# board.net
KiCad netlist of a schematic drawn in EAGLE
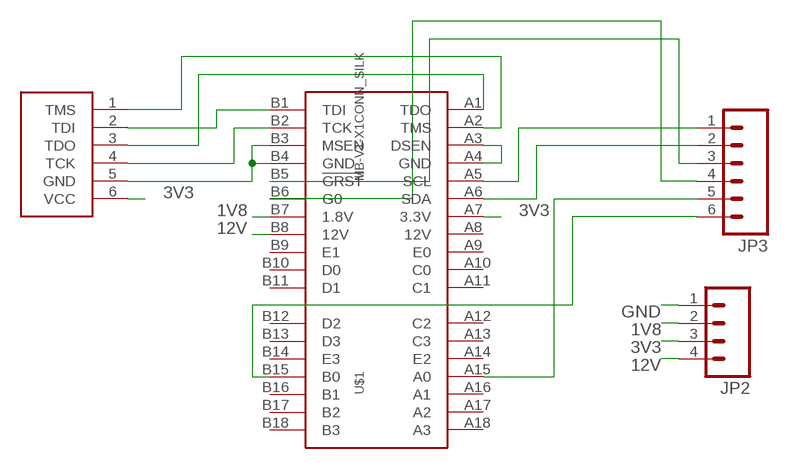
[diagram p0: schematic, sheet 1]

(export (version "E")
  (design (tool "Eeschema 10.0.6"))
  (components
    (comp (ref "JP2")
      (value "M04PTH")
      (footprint "eagle-import:1X04")
      (libsource (lib "eagle-import") (part "M04PTH"))
    )
    (comp (ref "JP3")
      (value "M06SIP")
      (footprint "eagle-import:1X06")
      (libsource (lib "eagle-import") (part "M06SIP"))
    )
    (comp (ref "U$1")
      (value "MB-V1-X1CONN_SILK")
      (footprint "eagle-import:MB-V1-X1-CONN")
      (libsource (lib "eagle-import") (part "MB-V1-X1CONN_SILK"))
    )
    (comp (ref "U$2")
      (value "JTAGDIGILENT")
      (footprint "eagle-import:1X06")
      (libsource (lib "eagle-import") (part "JTAGDIGILENT"))
    )
  )
  (nets
    (net (code "1") (name "/1V8") (class "Default")
      (node (ref "JP2") (pin "2") (pinfunction "2_2") (pintype "passive"))
      (node (ref "U$1") (pin "B7") (pinfunction "1.8V_B7") (pintype "bidirectional"))
    )
    (net (code "2") (name "/3V3") (class "Default")
      (node (ref "JP2") (pin "3") (pinfunction "3_3") (pintype "passive"))
      (node (ref "U$1") (pin "A7") (pinfunction "3.3V_A7") (pintype "bidirectional"))
      (node (ref "U$2") (pin "6") (pinfunction "VCC_6") (pintype "bidirectional"))
    )
    (net (code "3") (name "/12V") (class "Default")
      (node (ref "JP2") (pin "4") (pinfunction "4_4") (pintype "passive"))
      (node (ref "U$1") (pin "B8") (pinfunction "12V_B8") (pintype "bidirectional"))
    )
    (net (code "4") (name "/GND") (class "Default")
      (node (ref "JP2") (pin "1") (pinfunction "1_1") (pintype "passive"))
      (node (ref "U$1") (pin "B3") (pinfunction "MSEN_B3") (pintype "bidirectional"))
      (node (ref "U$1") (pin "B4") (pinfunction "GND_B4") (pintype "bidirectional"))
      (node (ref "U$2") (pin "5") (pinfunction "GND_5") (pintype "bidirectional"))
    )
    (net (code "5") (name "Net-(U$1-A0)") (class "Default")
      (node (ref "JP3") (pin "5") (pinfunction "5_5") (pintype "passive"))
      (node (ref "U$1") (pin "A15") (pinfunction "A0_A15") (pintype "bidirectional"))
    )
    (net (code "6") (name "Net-(U$1-B0)") (class "Default")
      (node (ref "JP3") (pin "6") (pinfunction "6_6") (pintype "passive"))
      (node (ref "U$1") (pin "B15") (pinfunction "B0_B15") (pintype "bidirectional"))
    )
    (net (code "7") (name "Net-(U$1-DSEN)") (class "Default")
      (node (ref "U$1") (pin "A3") (pinfunction "DSEN_A3") (pintype "bidirectional"))
      (node (ref "U$1") (pin "A4") (pinfunction "GND_A4") (pintype "bidirectional"))
    )
    (net (code "8") (name "Net-(U$1-G0)") (class "Default")
      (node (ref "JP3") (pin "4") (pinfunction "4_4") (pintype "passive"))
      (node (ref "U$1") (pin "B6") (pinfunction "G0_B6") (pintype "bidirectional"))
    )
    (net (code "9") (name "Net-(U$1-SCL)") (class "Default")
      (node (ref "JP3") (pin "1") (pinfunction "1_1") (pintype "passive"))
      (node (ref "U$1") (pin "A5") (pinfunction "SCL_A5") (pintype "bidirectional"))
    )
    (net (code "10") (name "Net-(U$1-SDA)") (class "Default")
      (node (ref "JP3") (pin "2") (pinfunction "2_2") (pintype "passive"))
      (node (ref "U$1") (pin "A6") (pinfunction "SDA_A6") (pintype "bidirectional"))
    )
    (net (code "11") (name "Net-(U$1-TCK)") (class "Default")
      (node (ref "U$1") (pin "B2") (pinfunction "TCK_B2") (pintype "bidirectional"))
      (node (ref "U$2") (pin "4") (pinfunction "TCK_4") (pintype "bidirectional"))
    )
    (net (code "12") (name "Net-(U$1-TDI)") (class "Default")
      (node (ref "U$1") (pin "B1") (pinfunction "TDI_B1") (pintype "bidirectional"))
      (node (ref "U$2") (pin "2") (pinfunction "TDI_2") (pintype "bidirectional"))
    )
    (net (code "13") (name "Net-(U$1-TDO)") (class "Default")
      (node (ref "U$1") (pin "A1") (pinfunction "TDO_A1") (pintype "bidirectional"))
      (node (ref "U$2") (pin "3") (pinfunction "TDO_3") (pintype "bidirectional"))
    )
    (net (code "14") (name "Net-(U$1-TMS)") (class "Default")
      (node (ref "U$1") (pin "A2") (pinfunction "TMS_A2") (pintype "bidirectional"))
      (node (ref "U$2") (pin "1") (pinfunction "TMS_1") (pintype "bidirectional"))
    )
    (net (code "15") (name "Net-(U$1-~{GRST})") (class "Default")
      (node (ref "JP3") (pin "3") (pinfunction "3_3") (pintype "passive"))
      (node (ref "U$1") (pin "B5") (pinfunction "~{GRST}_B5") (pintype "bidirectional"))
    )
    (net (code "16") (name "unconnected-(U$1-12V-PadA8)") (class "Default")
      (node (ref "U$1") (pin "A8") (pinfunction "12V_A8") (pintype "bidirectional"))
    )
    (net (code "17") (name "unconnected-(U$1-A1-PadA16)") (class "Default")
      (node (ref "U$1") (pin "A16") (pinfunction "A1_A16") (pintype "bidirectional"))
    )
    (net (code "18") (name "unconnected-(U$1-A2-PadA17)") (class "Default")
      (node (ref "U$1") (pin "A17") (pinfunction "A2_A17") (pintype "bidirectional"))
    )
    (net (code "19") (name "unconnected-(U$1-A3-PadA18)") (class "Default")
      (node (ref "U$1") (pin "A18") (pinfunction "A3_A18") (pintype "bidirectional"))
    )
    (net (code "20") (name "unconnected-(U$1-B1-PadB16)") (class "Default")
      (node (ref "U$1") (pin "B16") (pinfunction "B1_B16") (pintype "bidirectional"))
    )
    (net (code "21") (name "unconnected-(U$1-B2-PadB17)") (class "Default")
      (node (ref "U$1") (pin "B17") (pinfunction "B2_B17") (pintype "bidirectional"))
    )
    (net (code "22") (name "unconnected-(U$1-B3-PadB18)") (class "Default")
      (node (ref "U$1") (pin "B18") (pinfunction "B3_B18") (pintype "bidirectional"))
    )
    (net (code "23") (name "unconnected-(U$1-C0-PadA10)") (class "Default")
      (node (ref "U$1") (pin "A10") (pinfunction "C0_A10") (pintype "bidirectional"))
    )
    (net (code "24") (name "unconnected-(U$1-C1-PadA11)") (class "Default")
      (node (ref "U$1") (pin "A11") (pinfunction "C1_A11") (pintype "bidirectional"))
    )
    (net (code "25") (name "unconnected-(U$1-C2-PadA12)") (class "Default")
      (node (ref "U$1") (pin "A12") (pinfunction "C2_A12") (pintype "bidirectional"))
    )
    (net (code "26") (name "unconnected-(U$1-C3-PadA13)") (class "Default")
      (node (ref "U$1") (pin "A13") (pinfunction "C3_A13") (pintype "bidirectional"))
    )
    (net (code "27") (name "unconnected-(U$1-D0-PadB10)") (class "Default")
      (node (ref "U$1") (pin "B10") (pinfunction "D0_B10") (pintype "bidirectional"))
    )
    (net (code "28") (name "unconnected-(U$1-D1-PadB11)") (class "Default")
      (node (ref "U$1") (pin "B11") (pinfunction "D1_B11") (pintype "bidirectional"))
    )
    (net (code "29") (name "unconnected-(U$1-D2-PadB12)") (class "Default")
      (node (ref "U$1") (pin "B12") (pinfunction "D2_B12") (pintype "bidirectional"))
    )
    (net (code "30") (name "unconnected-(U$1-D3-PadB13)") (class "Default")
      (node (ref "U$1") (pin "B13") (pinfunction "D3_B13") (pintype "bidirectional"))
    )
    (net (code "31") (name "unconnected-(U$1-E0-PadA9)") (class "Default")
      (node (ref "U$1") (pin "A9") (pinfunction "E0_A9") (pintype "bidirectional"))
    )
    (net (code "32") (name "unconnected-(U$1-E1-PadB9)") (class "Default")
      (node (ref "U$1") (pin "B9") (pinfunction "E1_B9") (pintype "bidirectional"))
    )
    (net (code "33") (name "unconnected-(U$1-E2-PadA14)") (class "Default")
      (node (ref "U$1") (pin "A14") (pinfunction "E2_A14") (pintype "bidirectional"))
    )
    (net (code "34") (name "unconnected-(U$1-E3-PadB14)") (class "Default")
      (node (ref "U$1") (pin "B14") (pinfunction "E3_B14") (pintype "bidirectional"))
    )
  )
)
